# Auto-tune-FM-reciever-1_00.net
KiCad netlist of a schematic drawn in EasyEDA
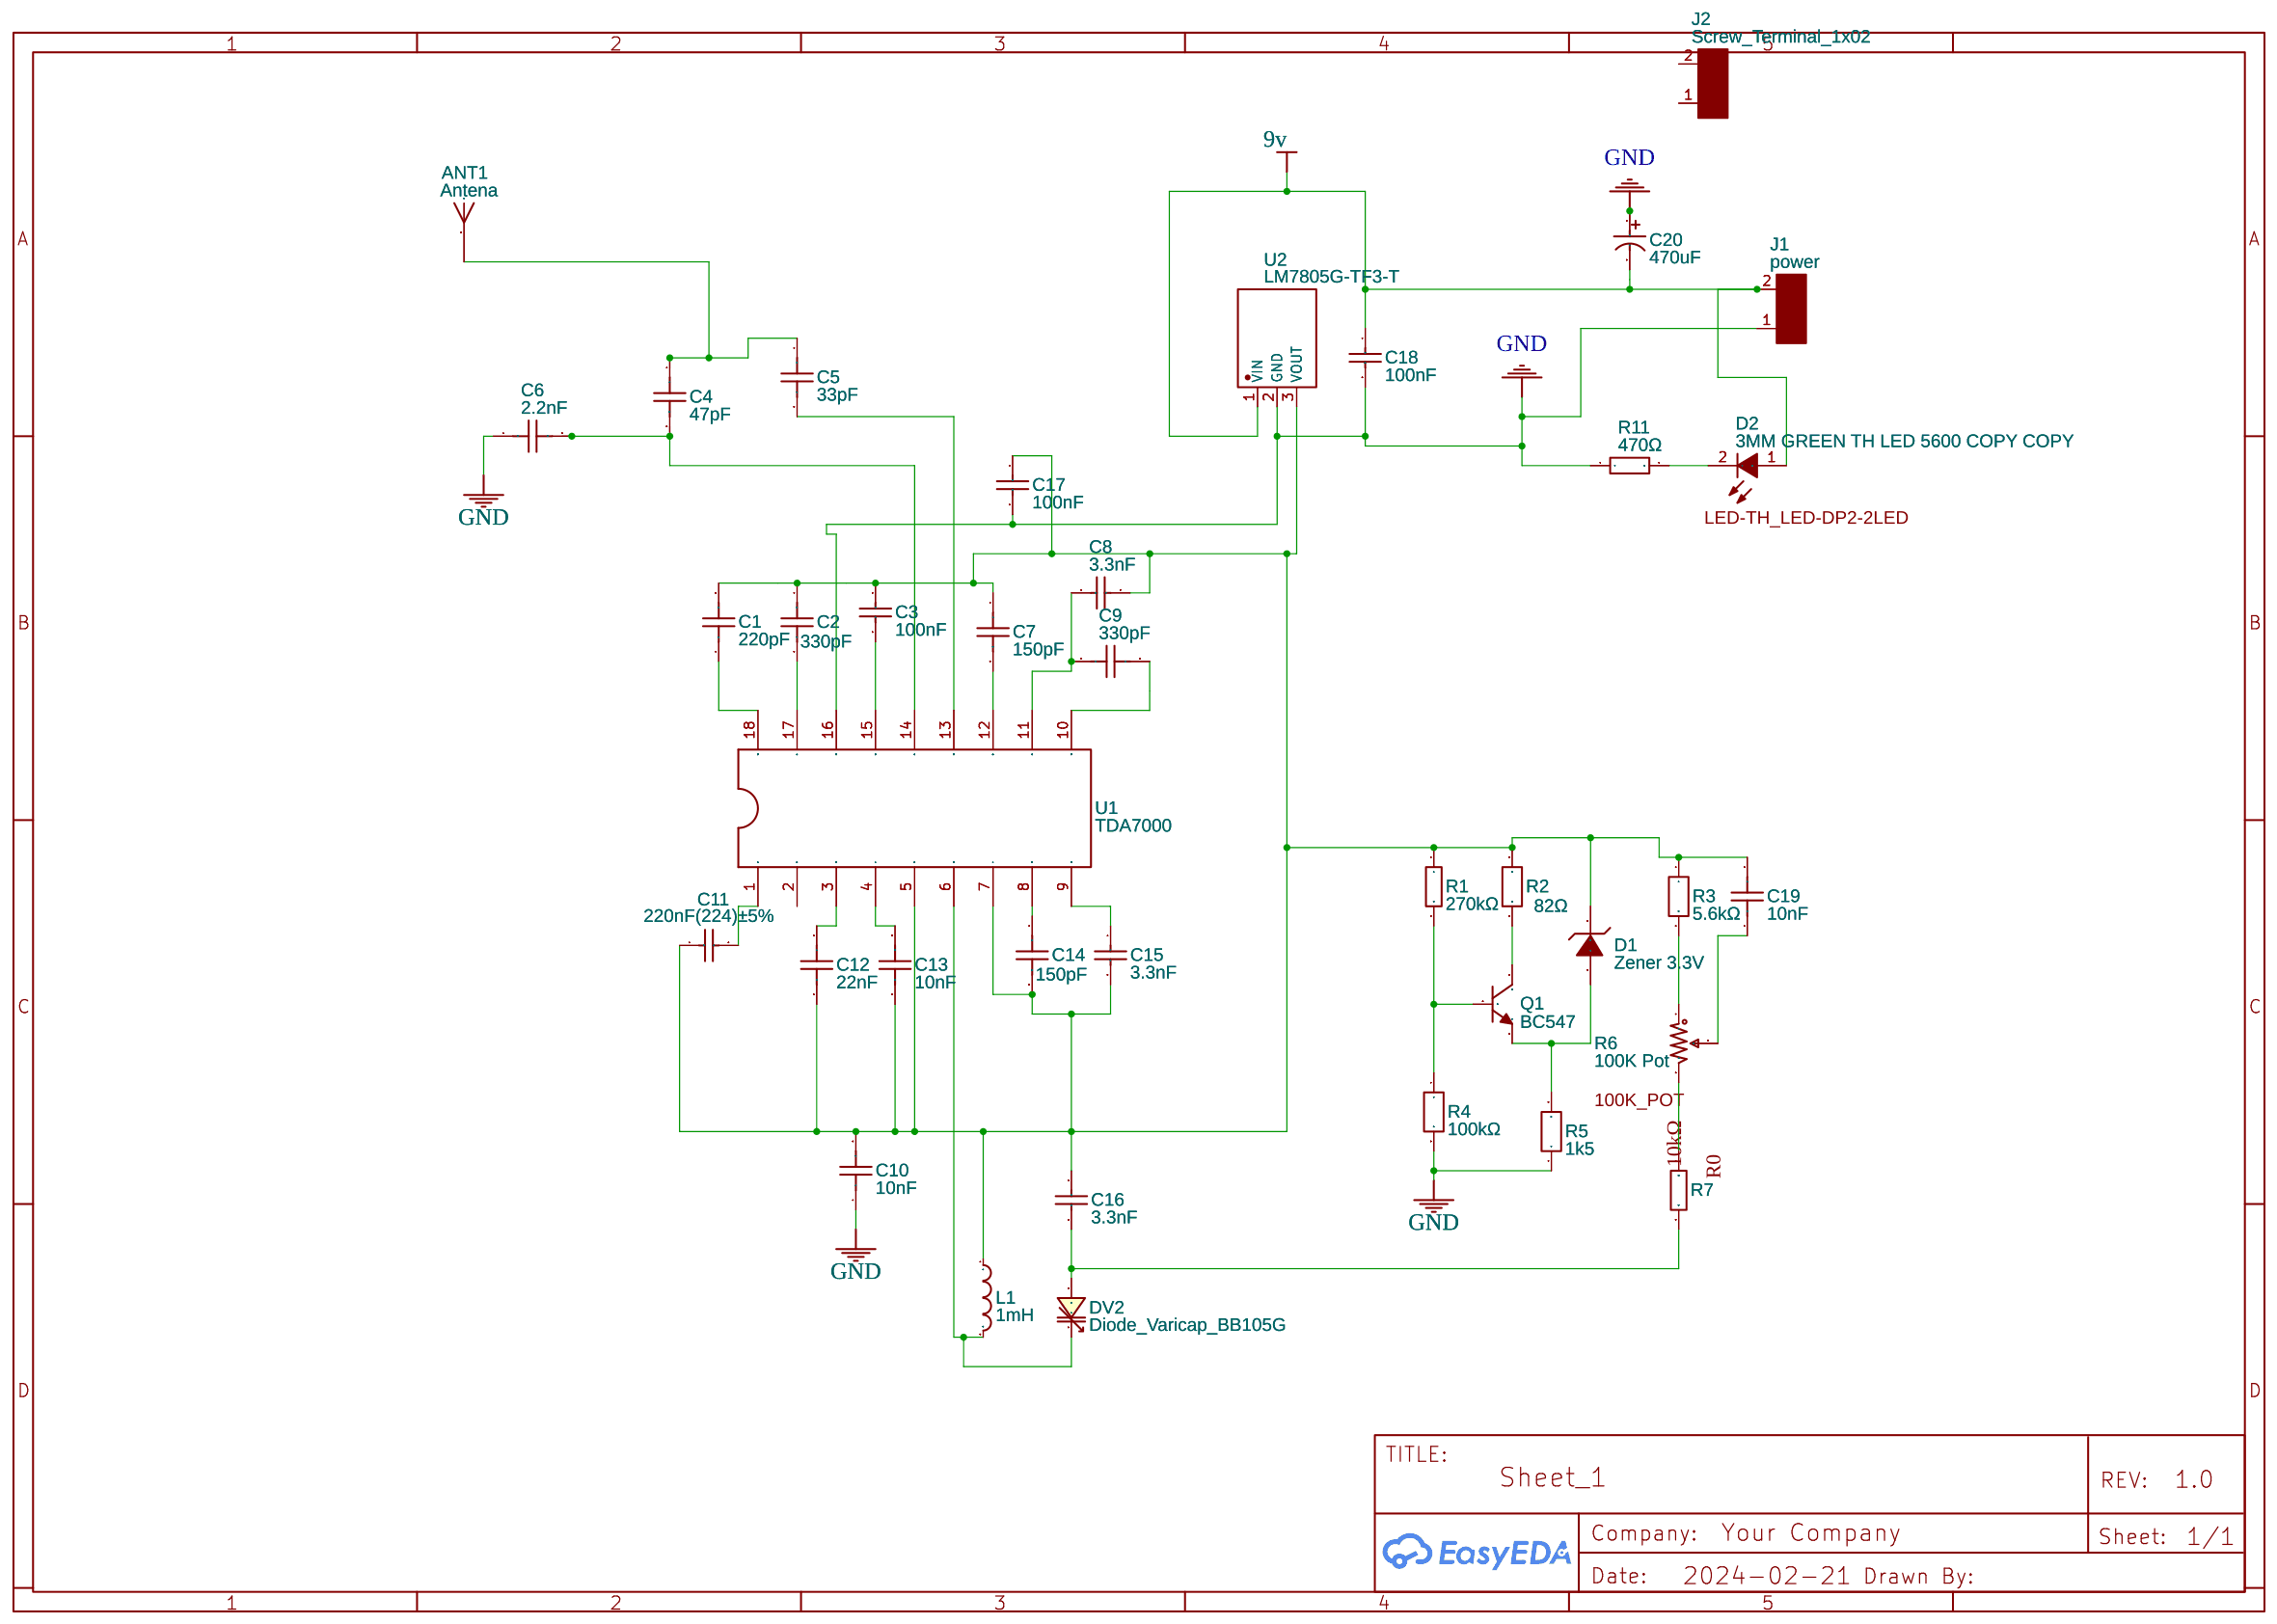
[diagram p0: schematic sheet]

(export (version "E")
  (design (tool "Eeschema 10.0.6"))
  (components
    (comp (ref "ANT1")
      (value "Antena")
      (fields (field (name "Manufacturer Part") "?"))
      (libsource (lib "") (part "Antena"))
    )
    (comp (ref "C1")
      (value "220pF")
      (fields (field (name "Manufacturer Part") "CT81N5Y5P1B221KSE") (field (name "Manufacturer") "FH(风华)"))
      (libsource (lib "") (part "CT81N5Y5P1B221KSE"))
    )
    (comp (ref "C2")
      (value "330pF")
      (fields
        (field (name "Manufacturer Part") "CC4-0805-CG-100V-330pF-J")
        (field (name "Manufacturer") "TORCH(火炬)")
      )
      (libsource (lib "") (part "CC4-0805-CG-100V-330PF-J"))
    )
    (comp (ref "C3")
      (value "100nF")
      (fields (field (name "Manufacturer Part") "0.1UF(104) +-20% 63v"))
      (libsource (lib "") (part "100nF"))
    )
    (comp (ref "C4")
      (value "47pF")
      (fields
        (field (name "Manufacturer Part") "CC4-0805-CG-50V-47pF-J")
        (field (name "Manufacturer") "TORCH(火炬)")
      )
      (libsource (lib "") (part "CC4-0805-CG -50V-47pF-J"))
    )
    (comp (ref "C5")
      (value "33pF")
      (fields
        (field (name "Manufacturer Part") "CC4-0805-CG-50V-33pF-J")
        (field (name "Manufacturer") "TORCH(火炬)")
      )
      (libsource (lib "") (part "CC4-0805-CG -50V-33pF-J"))
    )
    (comp (ref "C6")
      (value "2.2nF")
      (fields
        (field (name "Manufacturer Part") "CY1222ME1IEF47M0A2")
        (field (name "Manufacturer") "Dersonic(德尔创)")
      )
      (libsource (lib "") (part "CY1222ME1IEF47M0A2"))
    )
    (comp (ref "C7")
      (value "150pF")
      (fields
        (field (name "Manufacturer Part") "CC4-0805-CG-100V-150pF-J-L")
        (field (name "Manufacturer") "TORCH(火炬)")
      )
      (libsource (lib "") (part "CC4-0805-CG-100V-150PF-J-L"))
    )
    (comp (ref "C8")
      (value "3.3nF")
      (fields (field (name "Manufacturer Part") "332Z-50V-CCC") (field (name "Manufacturer") "LCSC"))
      (libsource (lib "") (part "3.3nF_1"))
    )
    (comp (ref "C9")
      (value "330pF")
      (fields
        (field (name "Manufacturer Part") "CC4-0805-CG-100V-330pF-J")
        (field (name "Manufacturer") "TORCH(火炬)")
      )
      (libsource (lib "") (part "CC4-0805-CG-100V-330PF-J_1"))
    )
    (comp (ref "C10")
      (value "10nF")
      (fields (field (name "Manufacturer Part") "MKS2C022201A00MSSD") (field (name "Manufacturer") "WIMA"))
      (libsource (lib "") (part "Capacitor 10nF #2"))
    )
    (comp (ref "C11")
      (value "220nF(224)±5%")
      (fields
        (field (name "Manufacturer Part") "CBBCapacitor 224J/630V")
        (field (name "Manufacturer") "ValuePro")
      )
      (libsource (lib "") (part "CBBCapacitor 224J/630V"))
    )
    (comp (ref "C12")
      (value "22nF")
      (fields (field (name "Manufacturer Part") "MKS2C022201A00MSSD") (field (name "Manufacturer") "WIMA"))
      (libsource (lib "") (part "Capacitor 22nF #7"))
    )
    (comp (ref "C13")
      (value "10nF")
      (fields (field (name "Manufacturer Part") "MKS2C022201A00MSSD") (field (name "Manufacturer") "WIMA"))
      (libsource (lib "") (part "Capacitor 10nF #2"))
    )
    (comp (ref "C14")
      (value "150pF")
      (fields
        (field (name "Manufacturer Part") "CC4-0805-CG-100V-150pF-J-L")
        (field (name "Manufacturer") "TORCH(火炬)")
      )
      (libsource (lib "") (part "CC4-0805-CG-100V-150PF-J-L"))
    )
    (comp (ref "C15")
      (value "3.3nF")
      (fields (field (name "Manufacturer Part") "332Z-50V-CCC") (field (name "Manufacturer") "LCSC"))
      (libsource (lib "") (part "3.3nF"))
    )
    (comp (ref "C16")
      (value "3.3nF")
      (fields (field (name "Manufacturer Part") "332Z-50V-CCC") (field (name "Manufacturer") "LCSC"))
      (libsource (lib "") (part "3.3nF"))
    )
    (comp (ref "C17")
      (value "100nF")
      (fields (field (name "Manufacturer Part") "0.1UF(104) +-20% 63v"))
      (libsource (lib "") (part "100nF"))
    )
    (comp (ref "C18")
      (value "100nF")
      (fields (field (name "Manufacturer Part") "0.1UF(104) +-20% 63v"))
      (libsource (lib "") (part "100nF"))
    )
    (comp (ref "C19")
      (value "10nF")
      (fields (field (name "Manufacturer Part") "MKS2C022201A00MSSD") (field (name "Manufacturer") "WIMA"))
      (libsource (lib "") (part "Capacitor 10nF #2"))
    )
    (comp (ref "C20")
      (value "470uF")
      (fields (field (name "Manufacturer Part") "470uf16v") (field (name "Manufacturer") "ValuePro"))
      (libsource (lib "") (part "470UF16V"))
    )
    (comp (ref "D1")
      (value "Zener 3.3V")
      (fields (field (name "Manufacturer Part") "Z7.5-CKD-3.3V@5mA"))
      (libsource (lib "") (part "Z7.5-CKD-3.3V@5MA"))
    )
    (comp (ref "D2")
      (value "3MM GREEN TH LED 5600 COPY COPY")
      (fields (field (name "Manufacturer Part") "5600") (field (name "Manufacturer") "VccLite"))
      (libsource (lib "") (part "3MM GREEN TH LED 5600 COPY COPY"))
    )
    (comp (ref "DV2") (value "Diode_Varicap_BB105G") (libsource (lib "") (part "Diode_Varicap_BB105G")))
    (comp (ref "J1") (value "power") (libsource (lib "") (part "Screw_Terminal_1x02")))
    (comp (ref "J2") (value "Screw_Terminal_1x02") (libsource (lib "") (part "Screw_Terminal_1x02")))
    (comp (ref "L1")
      (value "1mH")
      (fields
        (field (name "Manufacturer Part") "CKL0510-1mH/K-A-0.252MHz T")
        (field (name "Manufacturer") "CENKER(岑科)")
      )
      (libsource (lib "") (part "CKL0510-1MH/K-A-0.252MHZ T"))
    )
    (comp (ref "Q1")
      (value "BC547")
      (fields (field (name "Manufacturer") "CJ(江苏长电/长晶)"))
      (libsource (lib "") (part "BC547"))
    )
    (comp (ref "R1")
      (value "270kΩ")
      (fields (field (name "Manufacturer Part") "MF3WS-270KΩ±1% T") (field (name "Manufacturer") "CCO(千志电子)"))
      (libsource (lib "") (part "MF3WS-270KΩ±1% T"))
    )
    (comp (ref "R2")
      (value "82Ω")
      (fields (field (name "Manufacturer Part") "23J82RE") (field (name "Manufacturer") "Ohmite"))
      (libsource (lib "") (part "23J82RE"))
    )
    (comp (ref "R3")
      (value "5.6kΩ")
      (fields (field (name "Manufacturer Part") "23J5K6E") (field (name "Manufacturer") "Ohmite"))
      (libsource (lib "") (part "23J5K6E"))
    )
    (comp (ref "R4")
      (value "100kΩ")
      (libsource (lib "") (part "AXIAL RESISTOR 100K OHM - TH_BD2.3-L6.0-P10.00-D0.4"))
    )
    (comp (ref "R5") (value "1k5") (libsource (lib "") (part "R_0603_EU")))
    (comp (ref "R6")
      (value "100K Pot")
      (fields (field (name "Manufacturer") "Amazon"))
      (libsource (lib "") (part "100K Pot"))
    )
    (comp (ref "R7")
      (value "Resistor 10KΩ")
      (fields (field (name "Manufacturer Part") "Resistor 10kΩ"))
      (libsource (lib "") (part "Resistor 10KΩ"))
    )
    (comp (ref "R11")
      (value "470Ω")
      (fields (field (name "Manufacturer Part") "MFR-25JT-52-470R") (field (name "Manufacturer") "YAGEO(国巨)"))
      (libsource (lib "") (part "MFR-25JT-52-470R"))
    )
    (comp (ref "U1") (value "TDA7000") (libsource (lib "") (part "TDA7000")))
    (comp (ref "U2")
      (value "LM7805G-TF3-T")
      (fields (field (name "Manufacturer") "UTC(友顺)"))
      (libsource (lib "") (part "LM7805G-TF3-T"))
    )
  )
  (nets
    (net (code "1") (name "9v") (class "Default")
      (node (ref "C18") (pin "1") (pinfunction "1_1") (pintype "input"))
      (node (ref "C20") (pin "2") (pinfunction "2_2") (pintype "input"))
      (node (ref "D2") (pin "1") (pinfunction "A_1") (pintype "input"))
      (node (ref "J1") (pin "2") (pintype "unspecified"))
      (node (ref "U2") (pin "1") (pinfunction "VIN_1") (pintype "unspecified"))
    )
    (net (code "2") (name "GND") (class "Default")
      (node (ref "C10") (pin "1") (pinfunction "1_1") (pintype "unspecified"))
      (node (ref "C17") (pin "2") (pinfunction "2_2") (pintype "input"))
      (node (ref "C18") (pin "2") (pinfunction "2_2") (pintype "input"))
      (node (ref "C20") (pin "1") (pinfunction "1_1") (pintype "input"))
      (node (ref "C6") (pin "1") (pinfunction "1_1") (pintype "unspecified"))
      (node (ref "J1") (pin "1") (pintype "unspecified"))
      (node (ref "R11") (pin "1") (pinfunction "1_1") (pintype "unspecified"))
      (node (ref "R4") (pin "2") (pinfunction "2_2") (pintype "unspecified"))
      (node (ref "R5") (pin "1") (pinfunction "1_1") (pintype "unspecified"))
      (node (ref "U1") (pin "16") (pinfunction "16_16") (pintype "unspecified"))
      (node (ref "U2") (pin "2") (pinfunction "GND_2") (pintype "unspecified"))
    )
    (net (code "3") (name "Net-(ANT1-Pad1)") (class "Default")
      (node (ref "ANT1") (pin "1") (pinfunction "1_1") (pintype "unspecified"))
      (node (ref "C4") (pin "1") (pinfunction "1_1") (pintype "unspecified"))
      (node (ref "C5") (pin "1") (pinfunction "1_1") (pintype "unspecified"))
    )
    (net (code "4") (name "Net-(C1-Pad1)") (class "Default")
      (node (ref "C1") (pin "1") (pinfunction "1_1") (pintype "unspecified"))
      (node (ref "U1") (pin "18") (pinfunction "18_18") (pintype "unspecified"))
    )
    (net (code "5") (name "Net-(C2-Pad2)") (class "Default")
      (node (ref "C2") (pin "2") (pinfunction "2_2") (pintype "unspecified"))
      (node (ref "U1") (pin "17") (pinfunction "17_17") (pintype "unspecified"))
    )
    (net (code "6") (name "Net-(C3-Pad2)") (class "Default")
      (node (ref "C3") (pin "2") (pinfunction "2_2") (pintype "input"))
      (node (ref "U1") (pin "15") (pinfunction "15_15") (pintype "unspecified"))
    )
    (net (code "7") (name "Net-(C4-Pad2)") (class "Default")
      (node (ref "C4") (pin "2") (pinfunction "2_2") (pintype "unspecified"))
      (node (ref "C6") (pin "2") (pinfunction "2_2") (pintype "unspecified"))
      (node (ref "U1") (pin "14") (pinfunction "14_14") (pintype "unspecified"))
    )
    (net (code "8") (name "Net-(C5-Pad2)") (class "Default")
      (node (ref "C5") (pin "2") (pinfunction "2_2") (pintype "unspecified"))
      (node (ref "U1") (pin "13") (pinfunction "13_13") (pintype "unspecified"))
    )
    (net (code "9") (name "Net-(C7-Pad2)") (class "Default")
      (node (ref "C7") (pin "2") (pinfunction "2_2") (pintype "unspecified"))
      (node (ref "U1") (pin "12") (pinfunction "12_12") (pintype "unspecified"))
    )
    (net (code "10") (name "Net-(C8-Pad1)") (class "Default")
      (node (ref "C8") (pin "1") (pinfunction "1_1") (pintype "input"))
      (node (ref "C9") (pin "1") (pinfunction "1_1") (pintype "unspecified"))
      (node (ref "U1") (pin "11") (pinfunction "11_11") (pintype "unspecified"))
    )
    (net (code "11") (name "Net-(C9-Pad2)") (class "Default")
      (node (ref "C9") (pin "2") (pinfunction "2_2") (pintype "unspecified"))
      (node (ref "U1") (pin "10") (pinfunction "10_10") (pintype "unspecified"))
    )
    (net (code "12") (name "Net-(C11-Pad2)") (class "Default")
      (node (ref "C11") (pin "2") (pinfunction "2_2") (pintype "input"))
      (node (ref "U1") (pin "1") (pinfunction "1_1") (pintype "unspecified"))
    )
    (net (code "13") (name "Net-(C12-Pad2)") (class "Default")
      (node (ref "C12") (pin "2") (pinfunction "2_2") (pintype "unspecified"))
      (node (ref "U1") (pin "3") (pinfunction "3_3") (pintype "unspecified"))
    )
    (net (code "14") (name "Net-(C13-Pad2)") (class "Default")
      (node (ref "C13") (pin "2") (pinfunction "2_2") (pintype "unspecified"))
      (node (ref "U1") (pin "4") (pinfunction "4_4") (pintype "unspecified"))
    )
    (net (code "15") (name "Net-(C14-Pad1)") (class "Default")
      (node (ref "C14") (pin "1") (pinfunction "1_1") (pintype "unspecified"))
      (node (ref "U1") (pin "8") (pinfunction "8_8") (pintype "unspecified"))
    )
    (net (code "16") (name "Net-(C15-Pad1)") (class "Default")
      (node (ref "C15") (pin "1") (pinfunction "1_1") (pintype "input"))
      (node (ref "U1") (pin "9") (pinfunction "9_9") (pintype "unspecified"))
    )
    (net (code "17") (name "Net-(C19-Pad1)") (class "Default")
      (node (ref "C19") (pin "1") (pinfunction "1_1") (pintype "unspecified"))
      (node (ref "R6") (pin "2") (pinfunction "2_2") (pintype "unspecified"))
    )
    (net (code "18") (name "Net-(D1-A)") (class "Default")
      (node (ref "D1") (pin "1") (pinfunction "A_1") (pintype "unspecified"))
      (node (ref "Q1") (pin "3") (pinfunction "E_3") (pintype "unspecified"))
      (node (ref "R5") (pin "2") (pinfunction "2_2") (pintype "unspecified"))
    )
    (net (code "19") (name "Net-(D1-K)") (class "Default")
      (node (ref "C1") (pin "2") (pinfunction "2_2") (pintype "unspecified"))
      (node (ref "C10") (pin "2") (pinfunction "2_2") (pintype "unspecified"))
      (node (ref "C11") (pin "1") (pinfunction "1_1") (pintype "input"))
      (node (ref "C12") (pin "1") (pinfunction "1_1") (pintype "unspecified"))
      (node (ref "C13") (pin "1") (pinfunction "1_1") (pintype "unspecified"))
      (node (ref "C14") (pin "2") (pinfunction "2_2") (pintype "unspecified"))
      (node (ref "C15") (pin "2") (pinfunction "2_2") (pintype "input"))
      (node (ref "C16") (pin "1") (pinfunction "1_1") (pintype "input"))
      (node (ref "C17") (pin "1") (pinfunction "1_1") (pintype "input"))
      (node (ref "C19") (pin "2") (pinfunction "2_2") (pintype "unspecified"))
      (node (ref "C2") (pin "1") (pinfunction "1_1") (pintype "unspecified"))
      (node (ref "C3") (pin "1") (pinfunction "1_1") (pintype "input"))
      (node (ref "C7") (pin "1") (pinfunction "1_1") (pintype "unspecified"))
      (node (ref "C8") (pin "2") (pinfunction "2_2") (pintype "input"))
      (node (ref "D1") (pin "2") (pinfunction "K_2") (pintype "unspecified"))
      (node (ref "L1") (pin "1") (pinfunction "1_1") (pintype "unspecified"))
      (node (ref "R1") (pin "1") (pinfunction "1_1") (pintype "unspecified"))
      (node (ref "R2") (pin "1") (pinfunction "1_1") (pintype "unspecified"))
      (node (ref "R3") (pin "1") (pinfunction "1_1") (pintype "unspecified"))
      (node (ref "U1") (pin "5") (pinfunction "5_5") (pintype "unspecified"))
      (node (ref "U1") (pin "7") (pinfunction "7_7") (pintype "unspecified"))
      (node (ref "U2") (pin "3") (pinfunction "VOUT_3") (pintype "unspecified"))
    )
    (net (code "20") (name "Net-(D2-K)") (class "Default")
      (node (ref "D2") (pin "2") (pinfunction "K_2") (pintype "input"))
      (node (ref "R11") (pin "2") (pinfunction "2_2") (pintype "unspecified"))
    )
    (net (code "21") (name "Net-(DV2-A)") (class "Default")
      (node (ref "C16") (pin "2") (pinfunction "2_2") (pintype "input"))
      (node (ref "DV2") (pin "1") (pinfunction "A_1") (pintype "unspecified"))
      (node (ref "R7") (pin "2") (pinfunction "0_2") (pintype "input"))
    )
    (net (code "22") (name "Net-(DV2-K)") (class "Default")
      (node (ref "DV2") (pin "2") (pinfunction "K_2") (pintype "unspecified"))
      (node (ref "L1") (pin "2") (pinfunction "2_2") (pintype "unspecified"))
      (node (ref "U1") (pin "6") (pinfunction "6_6") (pintype "unspecified"))
    )
    (net (code "23") (name "Net-(Q1-B)") (class "Default")
      (node (ref "Q1") (pin "2") (pinfunction "B_2") (pintype "unspecified"))
      (node (ref "R1") (pin "2") (pinfunction "2_2") (pintype "unspecified"))
      (node (ref "R4") (pin "1") (pinfunction "1_1") (pintype "unspecified"))
    )
    (net (code "24") (name "Net-(Q1-C)") (class "Default")
      (node (ref "Q1") (pin "1") (pinfunction "C_1") (pintype "unspecified"))
      (node (ref "R2") (pin "2") (pinfunction "2_2") (pintype "unspecified"))
    )
    (net (code "25") (name "Net-(R3-Pad2)") (class "Default")
      (node (ref "R3") (pin "2") (pinfunction "2_2") (pintype "unspecified"))
      (node (ref "R6") (pin "1") (pinfunction "1_1") (pintype "unspecified"))
    )
    (net (code "26") (name "Net-(R6-Pad3)") (class "Default")
      (node (ref "R6") (pin "3") (pinfunction "3_3") (pintype "unspecified"))
      (node (ref "R7") (pin "1") (pinfunction "0_1") (pintype "input"))
    )
    (net (code "27") (name "unconnected-(J2-Pad1)") (class "Default")
      (node (ref "J2") (pin "1") (pintype "unspecified"))
    )
    (net (code "28") (name "unconnected-(J2-Pad2)") (class "Default")
      (node (ref "J2") (pin "2") (pintype "unspecified"))
    )
    (net (code "29") (name "unconnected-(U1-Pad2)") (class "Default")
      (node (ref "U1") (pin "2") (pinfunction "2_2") (pintype "unspecified"))
    )
  )
)
